# zulu_a7_2.net
KiCad netlist of a schematic drawn in Altium Designer
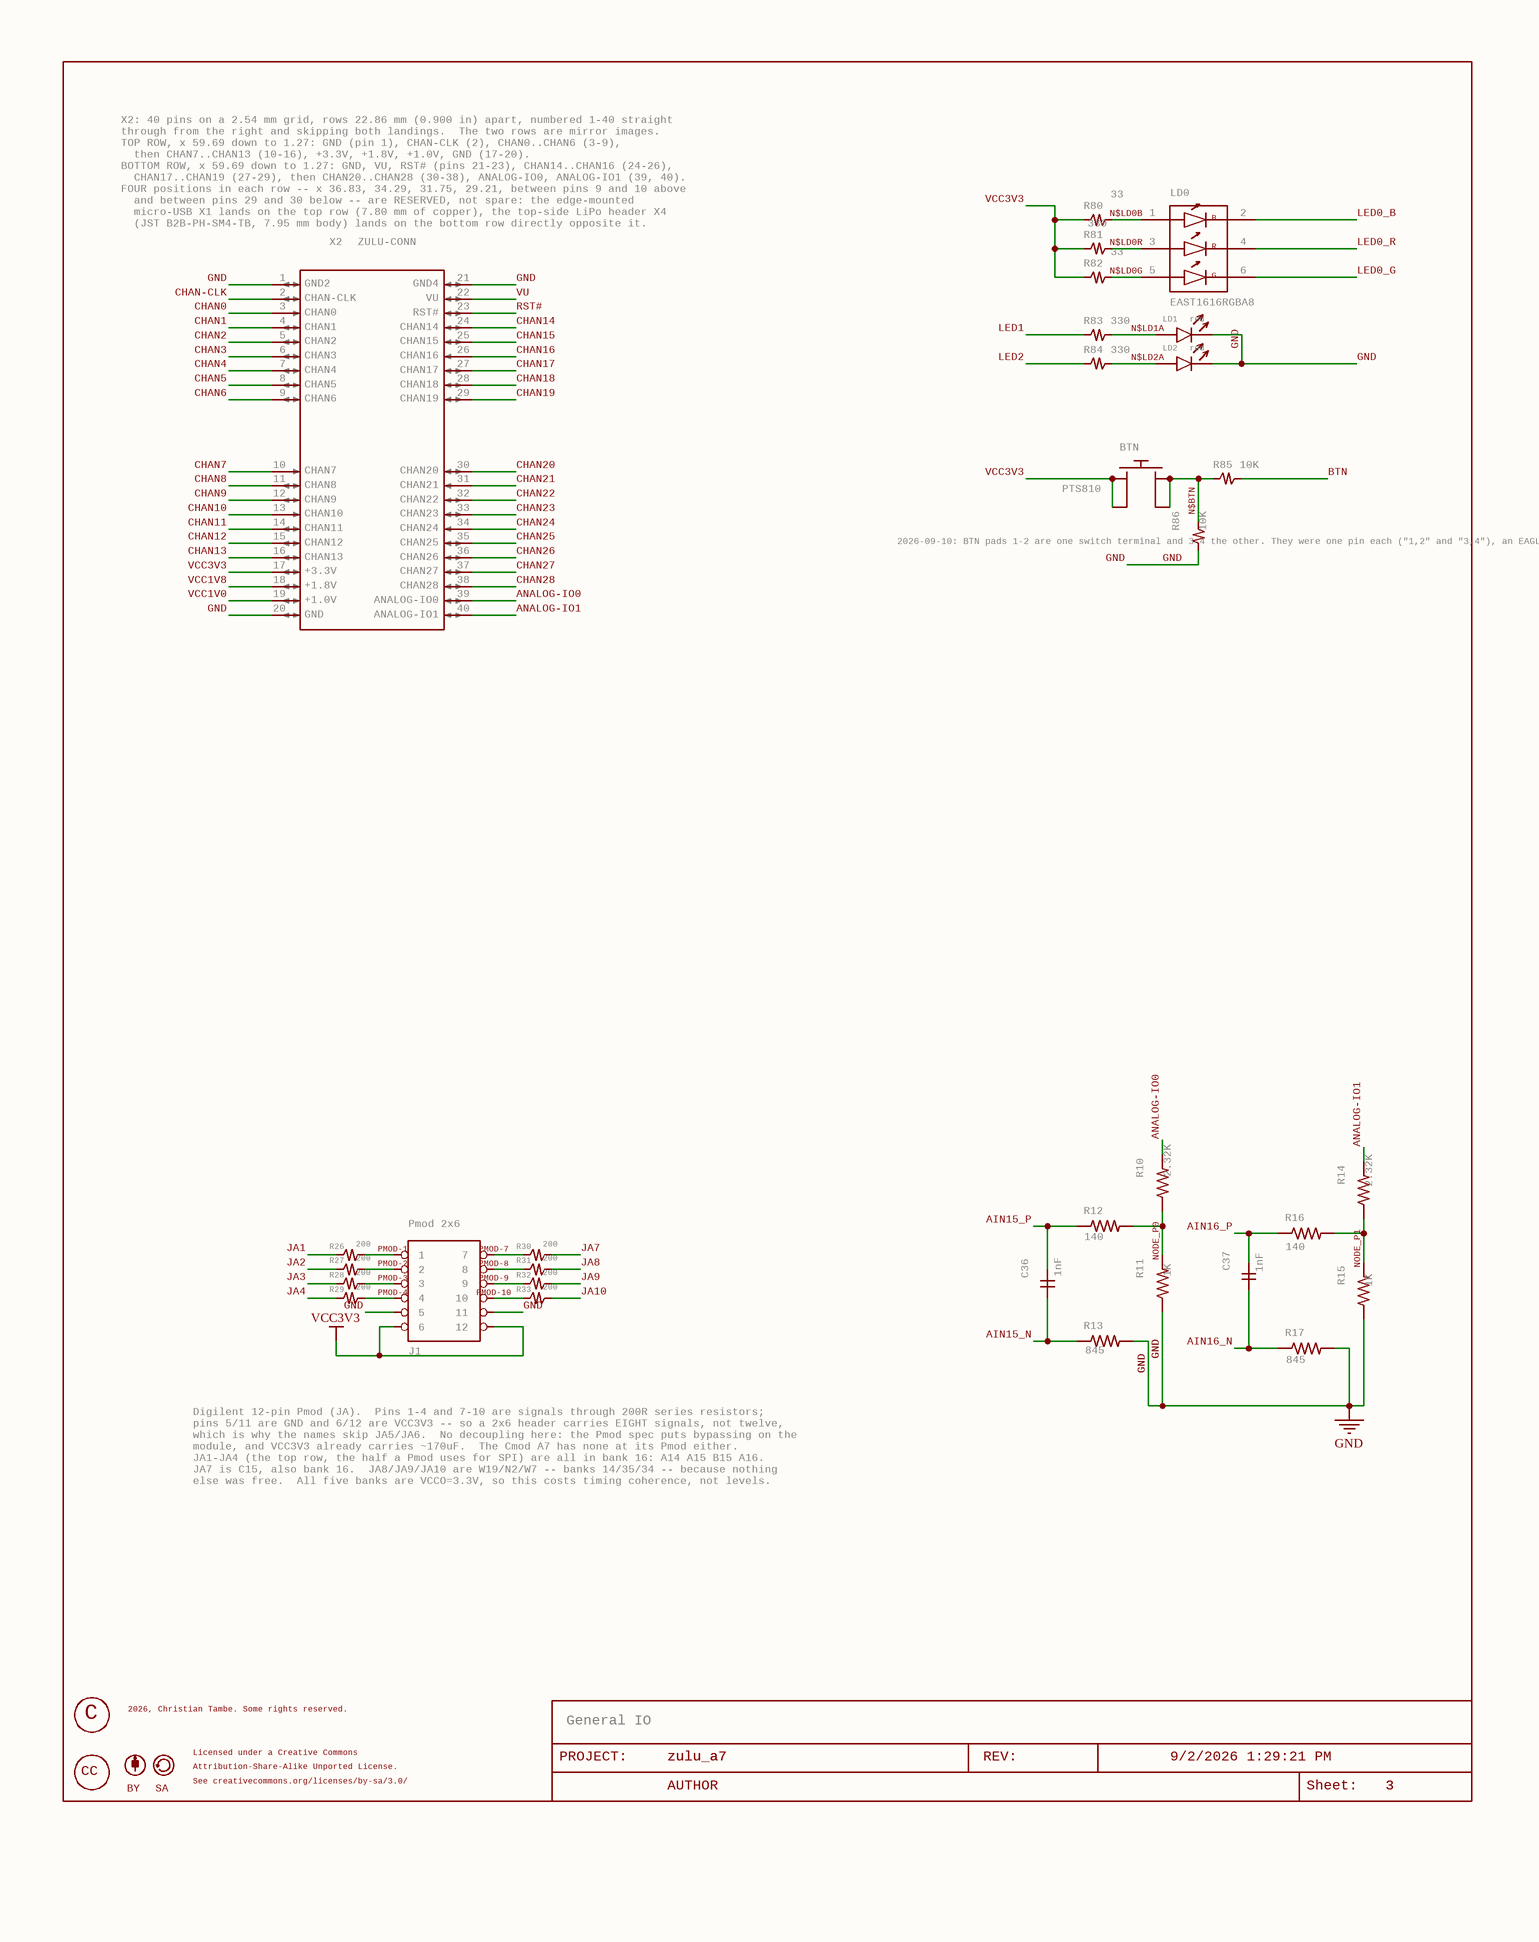
[diagram p0: zulu_a7_2.SchDoc]

(export (version "E")
  (design (tool "Eeschema 10.0.6"))
  (components
    (comp (ref "BTN")
      (value "PTS810")
      (footprint "PTS810")
      (fields (field (name "MANF") "Littelfuse (C&K)") (field (name "LIBRARYNAME") "ctambe"))
      (libsource (lib "ctambe") (part "SWITCH_TACT"))
    )
    (comp (ref "C36")
      (value "1nF")
      (footprint "C0402")
      (description "CAPACITOR, generic non-polarized, horizontal pins")
      (fields (field (name "MANF") "Murata"))
      (libsource (lib "rcl") (part "C-GENERICC0402"))
    )
    (comp (ref "C37")
      (value "1nF")
      (footprint "C0402")
      (description "CAPACITOR, generic non-polarized, horizontal pins")
      (fields (field (name "MANF") "Murata"))
      (libsource (lib "rcl") (part "C-GENERICC0402"))
    )
    (comp (ref "FRAME3")
      (value "DOCFIELD")
      (description "DOCUMENT FIELD")
      (fields
        (field (name "LAST_DATE_TIME") "9/2/2026 1:29:21 PM")
        (field (name "SHEET") "Sheet:")
        (field (name "SHEET_1") "3")
        (field (name "REV") "REV:")
        (field (name "PROJECT") "PROJECT:")
        (field (name "DRAWING_NAME") "zulu_a7")
        (field (name "AUTHOR") "AUTHOR")
        (field (name "DRAWING_NAME_1") "zulu_a7")
        (field (name "SHEET_2") "3")
        (field (name "LIBRARYNAME") "ctambe")
      )
      (libsource (lib "ctambe") (part "DOCFIELD"))
    )
    (comp (ref "J1")
      (value "Pmod 2x6")
      (footprint "2X06")
      (fields (field (name "MANF") "Sullins") (field (name "LIBRARYNAME") "ctambe"))
      (libsource (lib "ctambe") (part "PINHD-2X6"))
    )
    (comp (ref "LD0")
      (value "EAST1616RGBA8")
      (footprint "EVERLIGHT-19-337")
      (fields
        (field (name "B") "B")
        (field (name "R") "R")
        (field (name "G") "G")
        (field (name "MANF") "Everlight")
        (field (name "LIBRARYNAME") "ctambe")
      )
      (libsource (lib "ctambe") (part "LED_RGB"))
    )
    (comp (ref "LD1")
      (value "red")
      (footprint "LED0603")
      (description "LED")
      (fields (field (name "MANF") "Lite-On") (field (name "LIBRARYNAME") "ctambe"))
      (libsource (lib "ctambe") (part "LED"))
    )
    (comp (ref "LD2")
      (value "red")
      (footprint "LED0603")
      (description "LED")
      (fields (field (name "MANF") "Lite-On") (field (name "LIBRARYNAME") "ctambe"))
      (libsource (lib "ctambe") (part "LED"))
    )
    (comp (ref "R10")
      (value "2.32K")
      (footprint "R0201")
      (description "RESISTOR, American symbol")
      (fields (field (name "MANF") "Yageo"))
      (libsource (lib "rcl") (part "R-US_R0201"))
    )
    (comp (ref "R11")
      (value "1K")
      (footprint "R0201")
      (description "RESISTOR, American symbol")
      (fields (field (name "MANF") "Yageo"))
      (libsource (lib "rcl") (part "R-US_R0201"))
    )
    (comp (ref "R12")
      (value "140")
      (footprint "R0201")
      (description "RESISTOR, American symbol")
      (fields (field (name "MANF") "Yageo"))
      (libsource (lib "rcl") (part "R-US_R0201"))
    )
    (comp (ref "R13")
      (value "845")
      (footprint "R0201")
      (description "RESISTOR, American symbol")
      (fields (field (name "MANF") "Yageo"))
      (libsource (lib "rcl") (part "R-US_R0201"))
    )
    (comp (ref "R14")
      (value "2.32K")
      (footprint "R0201")
      (description "RESISTOR, American symbol")
      (fields (field (name "MANF") "Yageo"))
      (libsource (lib "rcl") (part "R-US_R0201"))
    )
    (comp (ref "R15")
      (value "1K")
      (footprint "R0201")
      (description "RESISTOR, American symbol")
      (fields (field (name "MANF") "Yageo"))
      (libsource (lib "rcl") (part "R-US_R0201"))
    )
    (comp (ref "R16")
      (value "140")
      (footprint "R0201")
      (description "RESISTOR, American symbol")
      (fields (field (name "MANF") "Yageo"))
      (libsource (lib "rcl") (part "R-US_R0201"))
    )
    (comp (ref "R17")
      (value "845")
      (footprint "R0201")
      (description "RESISTOR, American symbol")
      (fields (field (name "MANF") "Yageo"))
      (libsource (lib "rcl") (part "R-US_R0201"))
    )
    (comp (ref "R26")
      (value "200")
      (footprint "R0201")
      (description "RESISTOR, American symbol, small 2-zigzag variant (sheet 2 only)")
      (fields (field (name "MANF") "Yageo"))
      (libsource (lib "rcl") (part "R-US_SMALLR0201"))
    )
    (comp (ref "R27")
      (value "200")
      (footprint "R0201")
      (description "RESISTOR, American symbol, small 2-zigzag variant (sheet 2 only)")
      (fields (field (name "MANF") "Yageo"))
      (libsource (lib "rcl") (part "R-US_SMALLR0201"))
    )
    (comp (ref "R28")
      (value "200")
      (footprint "R0201")
      (description "RESISTOR, American symbol, small 2-zigzag variant (sheet 2 only)")
      (fields (field (name "MANF") "Yageo"))
      (libsource (lib "rcl") (part "R-US_SMALLR0201"))
    )
    (comp (ref "R29")
      (value "200")
      (footprint "R0201")
      (description "RESISTOR, American symbol, small 2-zigzag variant (sheet 2 only)")
      (fields (field (name "MANF") "Yageo"))
      (libsource (lib "rcl") (part "R-US_SMALLR0201"))
    )
    (comp (ref "R30")
      (value "200")
      (footprint "R0201")
      (description "RESISTOR, American symbol, small 2-zigzag variant (sheet 2 only)")
      (fields (field (name "MANF") "Yageo"))
      (libsource (lib "rcl") (part "R-US_SMALLR0201"))
    )
    (comp (ref "R31")
      (value "200")
      (footprint "R0201")
      (description "RESISTOR, American symbol, small 2-zigzag variant (sheet 2 only)")
      (fields (field (name "MANF") "Yageo"))
      (libsource (lib "rcl") (part "R-US_SMALLR0201"))
    )
    (comp (ref "R32")
      (value "200")
      (footprint "R0201")
      (description "RESISTOR, American symbol, small 2-zigzag variant (sheet 2 only)")
      (fields (field (name "MANF") "Yageo"))
      (libsource (lib "rcl") (part "R-US_SMALLR0201"))
    )
    (comp (ref "R33")
      (value "200")
      (footprint "R0201")
      (description "RESISTOR, American symbol, small 2-zigzag variant (sheet 2 only)")
      (fields (field (name "MANF") "Yageo"))
      (libsource (lib "rcl") (part "R-US_SMALLR0201"))
    )
    (comp (ref "R80")
      (value "33")
      (footprint "R0402")
      (description "RESISTOR, American symbol, small 2-zigzag variant (sheet 2 only)")
      (fields (field (name "MANF") "Yageo"))
      (libsource (lib "rcl") (part "R-US_SMALLR0402"))
    )
    (comp (ref "R81")
      (value "330")
      (footprint "R0402")
      (description "RESISTOR, American symbol, small 2-zigzag variant (sheet 2 only)")
      (fields (field (name "MANF") "Yageo"))
      (libsource (lib "rcl") (part "R-US_SMALLR0402"))
    )
    (comp (ref "R82")
      (value "33")
      (footprint "R0402")
      (description "RESISTOR, American symbol, small 2-zigzag variant (sheet 2 only)")
      (fields (field (name "MANF") "Yageo"))
      (libsource (lib "rcl") (part "R-US_SMALLR0402"))
    )
    (comp (ref "R83")
      (value "330")
      (footprint "R0402")
      (description "RESISTOR, American symbol, small 2-zigzag variant (sheet 2 only)")
      (fields (field (name "MANF") "Yageo"))
      (libsource (lib "rcl") (part "R-US_SMALLR0402"))
    )
    (comp (ref "R84")
      (value "330")
      (footprint "R0402")
      (description "RESISTOR, American symbol, small 2-zigzag variant (sheet 2 only)")
      (fields (field (name "MANF") "Yageo"))
      (libsource (lib "rcl") (part "R-US_SMALLR0402"))
    )
    (comp (ref "R85")
      (value "10K")
      (footprint "R0402")
      (description "RESISTOR, American symbol, small 2-zigzag variant (sheet 2 only)")
      (fields (field (name "MANF") "Yageo"))
      (libsource (lib "rcl") (part "R-US_SMALLR0402"))
    )
    (comp (ref "R86")
      (value "10K")
      (footprint "R0402")
      (description "RESISTOR, American symbol, small 2-zigzag variant (sheet 2 only)")
      (fields (field (name "MANF") "Yageo"))
      (libsource (lib "rcl") (part "R-US_SMALLR0402"))
    )
    (comp (ref "U$2")
      (value "CC_CC")
      (footprint "CC_CC")
      (fields (field (name "CC") "CC") (field (name "LIBRARYNAME") "ctambe"))
      (libsource (lib "ctambe") (part "CC_CC"))
    )
    (comp (ref "U$3")
      (value "CC_BY")
      (footprint "CC_BY")
      (fields (field (name "BY") "BY") (field (name "LIBRARYNAME") "ctambe"))
      (libsource (lib "ctambe") (part "CC_BY"))
    )
    (comp (ref "U$4")
      (value "CC_SA")
      (footprint "CC_SA")
      (fields (field (name "SA") "SA") (field (name "LIBRARYNAME") "ctambe"))
      (libsource (lib "ctambe") (part "CC_SA"))
    )
    (comp (ref "U$5")
      (value "CC_COPYRIGHT")
      (footprint "CC_COPYRIGHT")
      (fields (field (name "C") "C") (field (name "LIBRARYNAME") "ctambe"))
      (libsource (lib "ctambe") (part "CC_COPYRIGHT"))
    )
    (comp (ref "X2")
      (value "ZULU-CONN")
      (footprint "ZULU-DIP37")
      (description "Zulu A7 Board Connector")
      (fields
        (field (name "GATE") "CHAN-CLK")
        (field (name "MANF") "Sullins")
        (field (name "PART") "X2")
        (field (name "LIBRARYNAME") "ctambe")
      )
      (libsource (lib "ctambe") (part "ZULU-CONN"))
    )
  )
  (nets
    (net (code "1") (name "/AIN15_N") (class "Default")
      (node (ref "C36") (pin "1") (pinfunction "1_1") (pintype "passive"))
      (node (ref "R13") (pin "1") (pinfunction "1_1") (pintype "passive"))
    )
    (net (code "2") (name "/AIN15_P") (class "Default")
      (node (ref "C36") (pin "2") (pinfunction "2_2") (pintype "passive"))
      (node (ref "R12") (pin "1") (pinfunction "1_1") (pintype "passive"))
    )
    (net (code "3") (name "/AIN16_N") (class "Default")
      (node (ref "C37") (pin "1") (pinfunction "1_1") (pintype "passive"))
      (node (ref "R17") (pin "1") (pinfunction "1_1") (pintype "passive"))
    )
    (net (code "4") (name "/AIN16_P") (class "Default")
      (node (ref "C37") (pin "2") (pinfunction "2_2") (pintype "passive"))
      (node (ref "R16") (pin "1") (pinfunction "1_1") (pintype "passive"))
    )
    (net (code "5") (name "/ANALOG-IO0") (class "Default")
      (node (ref "R10") (pin "2") (pinfunction "2_2") (pintype "passive"))
      (node (ref "X2") (pin "39") (pinfunction "1_39") (pintype "bidirectional"))
    )
    (net (code "6") (name "/ANALOG-IO1") (class "Default")
      (node (ref "R14") (pin "2") (pinfunction "2_2") (pintype "passive"))
      (node (ref "X2") (pin "40") (pinfunction "1_40") (pintype "bidirectional"))
    )
    (net (code "7") (name "/BTN") (class "Default")
      (node (ref "R85") (pin "2") (pinfunction "2_2") (pintype "passive"))
    )
    (net (code "8") (name "/CHAN-CLK") (class "Default")
      (node (ref "X2") (pin "2") (pinfunction "1_2") (pintype "bidirectional"))
    )
    (net (code "9") (name "/CHAN0") (class "Default")
      (node (ref "X2") (pin "3") (pinfunction "1_3") (pintype "input"))
    )
    (net (code "10") (name "/CHAN1") (class "Default")
      (node (ref "X2") (pin "4") (pinfunction "1_4") (pintype "bidirectional"))
    )
    (net (code "11") (name "/CHAN2") (class "Default")
      (node (ref "X2") (pin "5") (pinfunction "1_5") (pintype "bidirectional"))
    )
    (net (code "12") (name "/CHAN3") (class "Default")
      (node (ref "X2") (pin "6") (pinfunction "1_6") (pintype "bidirectional"))
    )
    (net (code "13") (name "/CHAN4") (class "Default")
      (node (ref "X2") (pin "7") (pinfunction "1_7") (pintype "bidirectional"))
    )
    (net (code "14") (name "/CHAN5") (class "Default")
      (node (ref "X2") (pin "8") (pinfunction "1_8") (pintype "bidirectional"))
    )
    (net (code "15") (name "/CHAN6") (class "Default")
      (node (ref "X2") (pin "9") (pinfunction "1_9") (pintype "bidirectional"))
    )
    (net (code "16") (name "/CHAN7") (class "Default")
      (node (ref "X2") (pin "10") (pinfunction "1_10") (pintype "input"))
    )
    (net (code "17") (name "/CHAN8") (class "Default")
      (node (ref "X2") (pin "11") (pinfunction "1_11") (pintype "passive"))
    )
    (net (code "18") (name "/CHAN9") (class "Default")
      (node (ref "X2") (pin "12") (pinfunction "1_12") (pintype "bidirectional"))
    )
    (net (code "19") (name "/CHAN10") (class "Default")
      (node (ref "X2") (pin "13") (pinfunction "1_13") (pintype "input"))
    )
    (net (code "20") (name "/CHAN11") (class "Default")
      (node (ref "X2") (pin "14") (pinfunction "1_14") (pintype "bidirectional"))
    )
    (net (code "21") (name "/CHAN12") (class "Default")
      (node (ref "X2") (pin "15") (pinfunction "1_15") (pintype "bidirectional"))
    )
    (net (code "22") (name "/CHAN13") (class "Default")
      (node (ref "X2") (pin "16") (pinfunction "1_16") (pintype "bidirectional"))
    )
    (net (code "23") (name "/CHAN14") (class "Default")
      (node (ref "X2") (pin "24") (pinfunction "1_24") (pintype "bidirectional"))
    )
    (net (code "24") (name "/CHAN15") (class "Default")
      (node (ref "X2") (pin "25") (pinfunction "1_25") (pintype "bidirectional"))
    )
    (net (code "25") (name "/CHAN16") (class "Default")
      (node (ref "X2") (pin "26") (pinfunction "1_26") (pintype "input"))
    )
    (net (code "26") (name "/CHAN17") (class "Default")
      (node (ref "X2") (pin "27") (pinfunction "1_27") (pintype "bidirectional"))
    )
    (net (code "27") (name "/CHAN18") (class "Default")
      (node (ref "X2") (pin "28") (pinfunction "1_28") (pintype "bidirectional"))
    )
    (net (code "28") (name "/CHAN19") (class "Default")
      (node (ref "X2") (pin "29") (pinfunction "1_29") (pintype "bidirectional"))
    )
    (net (code "29") (name "/CHAN20") (class "Default")
      (node (ref "X2") (pin "30") (pinfunction "1_30") (pintype "bidirectional"))
    )
    (net (code "30") (name "/CHAN21") (class "Default")
      (node (ref "X2") (pin "31") (pinfunction "1_31") (pintype "input"))
    )
    (net (code "31") (name "/CHAN22") (class "Default")
      (node (ref "X2") (pin "32") (pinfunction "1_32") (pintype "bidirectional"))
    )
    (net (code "32") (name "/CHAN23") (class "Default")
      (node (ref "X2") (pin "33") (pinfunction "1_33") (pintype "bidirectional"))
    )
    (net (code "33") (name "/CHAN24") (class "Default")
      (node (ref "X2") (pin "34") (pinfunction "1_34") (pintype "input"))
    )
    (net (code "34") (name "/CHAN25") (class "Default")
      (node (ref "X2") (pin "35") (pinfunction "1_35") (pintype "bidirectional"))
    )
    (net (code "35") (name "/CHAN26") (class "Default")
      (node (ref "X2") (pin "36") (pinfunction "1_36") (pintype "bidirectional"))
    )
    (net (code "36") (name "/CHAN27") (class "Default")
      (node (ref "X2") (pin "37") (pinfunction "1_37") (pintype "bidirectional"))
    )
    (net (code "37") (name "/CHAN28") (class "Default")
      (node (ref "X2") (pin "38") (pinfunction "1_38") (pintype "bidirectional"))
    )
    (net (code "38") (name "/JA1") (class "Default")
      (node (ref "R26") (pin "1") (pinfunction "1_1") (pintype "passive"))
    )
    (net (code "39") (name "/JA2") (class "Default")
      (node (ref "R27") (pin "1") (pinfunction "1_1") (pintype "passive"))
    )
    (net (code "40") (name "/JA3") (class "Default")
      (node (ref "R28") (pin "1") (pinfunction "1_1") (pintype "passive"))
    )
    (net (code "41") (name "/JA4") (class "Default")
      (node (ref "R29") (pin "1") (pinfunction "1_1") (pintype "passive"))
    )
    (net (code "42") (name "/JA7") (class "Default")
      (node (ref "R30") (pin "2") (pinfunction "2_2") (pintype "passive"))
    )
    (net (code "43") (name "/JA8") (class "Default")
      (node (ref "R31") (pin "2") (pinfunction "2_2") (pintype "passive"))
    )
    (net (code "44") (name "/JA9") (class "Default")
      (node (ref "R32") (pin "2") (pinfunction "2_2") (pintype "passive"))
    )
    (net (code "45") (name "/JA10") (class "Default")
      (node (ref "R33") (pin "2") (pinfunction "2_2") (pintype "passive"))
    )
    (net (code "46") (name "/LED0_B") (class "Default")
      (node (ref "LD0") (pin "2") (pinfunction "2_2") (pintype "passive"))
    )
    (net (code "47") (name "/LED0_G") (class "Default")
      (node (ref "LD0") (pin "6") (pinfunction "6_6") (pintype "passive"))
    )
    (net (code "48") (name "/LED0_R") (class "Default")
      (node (ref "LD0") (pin "4") (pinfunction "4_4") (pintype "passive"))
    )
    (net (code "49") (name "/LED1") (class "Default")
      (node (ref "R83") (pin "1") (pinfunction "1_1") (pintype "passive"))
    )
    (net (code "50") (name "/LED2") (class "Default")
      (node (ref "R84") (pin "1") (pinfunction "1_1") (pintype "passive"))
    )
    (net (code "51") (name "/N$BTN") (class "Default")
      (node (ref "BTN") (pin "3") (pinfunction "2_3") (pintype "passive"))
      (node (ref "BTN") (pin "4") (pinfunction "2_4") (pintype "passive"))
      (node (ref "R85") (pin "1") (pinfunction "1_1") (pintype "passive"))
      (node (ref "R86") (pin "2") (pinfunction "2_2") (pintype "passive"))
    )
    (net (code "52") (name "/N$LD0B") (class "Default")
      (node (ref "LD0") (pin "1") (pinfunction "1_1") (pintype "passive"))
      (node (ref "R80") (pin "2") (pinfunction "2_2") (pintype "passive"))
    )
    (net (code "53") (name "/N$LD0G") (class "Default")
      (node (ref "LD0") (pin "5") (pinfunction "5_5") (pintype "passive"))
      (node (ref "R82") (pin "2") (pinfunction "2_2") (pintype "passive"))
    )
    (net (code "54") (name "/N$LD0R") (class "Default")
      (node (ref "LD0") (pin "3") (pinfunction "3_3") (pintype "passive"))
      (node (ref "R81") (pin "2") (pinfunction "2_2") (pintype "passive"))
    )
    (net (code "55") (name "/N$LD1A") (class "Default")
      (node (ref "LD1") (pin "A") (pinfunction "A_A") (pintype "passive"))
      (node (ref "R83") (pin "2") (pinfunction "2_2") (pintype "passive"))
    )
    (net (code "56") (name "/N$LD2A") (class "Default")
      (node (ref "LD2") (pin "A") (pinfunction "A_A") (pintype "passive"))
      (node (ref "R84") (pin "2") (pinfunction "2_2") (pintype "passive"))
    )
    (net (code "57") (name "/NODE_P0") (class "Default")
      (node (ref "R10") (pin "1") (pinfunction "1_1") (pintype "passive"))
      (node (ref "R11") (pin "2") (pinfunction "2_2") (pintype "passive"))
      (node (ref "R12") (pin "2") (pinfunction "2_2") (pintype "passive"))
    )
    (net (code "58") (name "/NODE_P1") (class "Default")
      (node (ref "R14") (pin "1") (pinfunction "1_1") (pintype "passive"))
      (node (ref "R15") (pin "2") (pinfunction "2_2") (pintype "passive"))
      (node (ref "R16") (pin "2") (pinfunction "2_2") (pintype "passive"))
    )
    (net (code "59") (name "/PMOD-1") (class "Default")
      (node (ref "J1") (pin "1") (pinfunction "1_1") (pintype "passive"))
      (node (ref "R26") (pin "2") (pinfunction "2_2") (pintype "passive"))
    )
    (net (code "60") (name "/PMOD-2") (class "Default")
      (node (ref "J1") (pin "2") (pinfunction "2_2") (pintype "passive"))
      (node (ref "R27") (pin "2") (pinfunction "2_2") (pintype "passive"))
    )
    (net (code "61") (name "/PMOD-3") (class "Default")
      (node (ref "J1") (pin "3") (pinfunction "3_3") (pintype "passive"))
      (node (ref "R28") (pin "2") (pinfunction "2_2") (pintype "passive"))
    )
    (net (code "62") (name "/PMOD-4") (class "Default")
      (node (ref "J1") (pin "4") (pinfunction "4_4") (pintype "passive"))
      (node (ref "R29") (pin "2") (pinfunction "2_2") (pintype "passive"))
    )
    (net (code "63") (name "/PMOD-7") (class "Default")
      (node (ref "J1") (pin "7") (pinfunction "7_7") (pintype "passive"))
      (node (ref "R30") (pin "1") (pinfunction "1_1") (pintype "passive"))
    )
    (net (code "64") (name "/PMOD-8") (class "Default")
      (node (ref "J1") (pin "8") (pinfunction "8_8") (pintype "passive"))
      (node (ref "R31") (pin "1") (pinfunction "1_1") (pintype "passive"))
    )
    (net (code "65") (name "/PMOD-9") (class "Default")
      (node (ref "J1") (pin "9") (pinfunction "9_9") (pintype "passive"))
      (node (ref "R32") (pin "1") (pinfunction "1_1") (pintype "passive"))
    )
    (net (code "66") (name "/PMOD-10") (class "Default")
      (node (ref "J1") (pin "10") (pinfunction "10_10") (pintype "passive"))
      (node (ref "R33") (pin "1") (pinfunction "1_1") (pintype "passive"))
    )
    (net (code "67") (name "/RST#") (class "Default")
      (node (ref "X2") (pin "23") (pinfunction "1_23") (pintype "bidirectional"))
    )
    (net (code "68") (name "/VCC1V0") (class "Default")
      (node (ref "X2") (pin "19") (pinfunction "1_19") (pintype "bidirectional"))
    )
    (net (code "69") (name "/VCC1V8") (class "Default")
      (node (ref "X2") (pin "18") (pinfunction "1_18") (pintype "bidirectional"))
    )
    (net (code "70") (name "/VU") (class "Default")
      (node (ref "X2") (pin "22") (pinfunction "1_22") (pintype "bidirectional"))
    )
    (net (code "71") (name "GND") (class "Default")
      (node (ref "J1") (pin "11") (pinfunction "11_11") (pintype "passive"))
      (node (ref "J1") (pin "5") (pinfunction "5_5") (pintype "passive"))
      (node (ref "LD1") (pin "K") (pinfunction "K_K") (pintype "passive"))
      (node (ref "LD2") (pin "K") (pinfunction "K_K") (pintype "passive"))
      (node (ref "R11") (pin "1") (pinfunction "1_1") (pintype "passive"))
      (node (ref "R13") (pin "2") (pinfunction "2_2") (pintype "passive"))
      (node (ref "R15") (pin "1") (pinfunction "1_1") (pintype "passive"))
      (node (ref "R17") (pin "2") (pinfunction "2_2") (pintype "passive"))
      (node (ref "R86") (pin "1") (pinfunction "1_1") (pintype "passive"))
      (node (ref "X2") (pin "1") (pinfunction "1_1") (pintype "bidirectional"))
      (node (ref "X2") (pin "20") (pinfunction "1_20") (pintype "bidirectional"))
      (node (ref "X2") (pin "21") (pinfunction "1_21") (pintype "bidirectional"))
    )
    (net (code "72") (name "VCC3V3") (class "Default")
      (node (ref "BTN") (pin "1") (pinfunction "1_1") (pintype "passive"))
      (node (ref "BTN") (pin "2") (pinfunction "1_2") (pintype "passive"))
      (node (ref "J1") (pin "12") (pinfunction "12_12") (pintype "passive"))
      (node (ref "J1") (pin "6") (pinfunction "6_6") (pintype "passive"))
      (node (ref "R80") (pin "1") (pinfunction "1_1") (pintype "passive"))
      (node (ref "R81") (pin "1") (pinfunction "1_1") (pintype "passive"))
      (node (ref "R82") (pin "1") (pinfunction "1_1") (pintype "passive"))
      (node (ref "X2") (pin "17") (pinfunction "1_17") (pintype "bidirectional"))
    )
  )
)
